# Power.net
KiCad netlist of a schematic drawn in Altium Designer
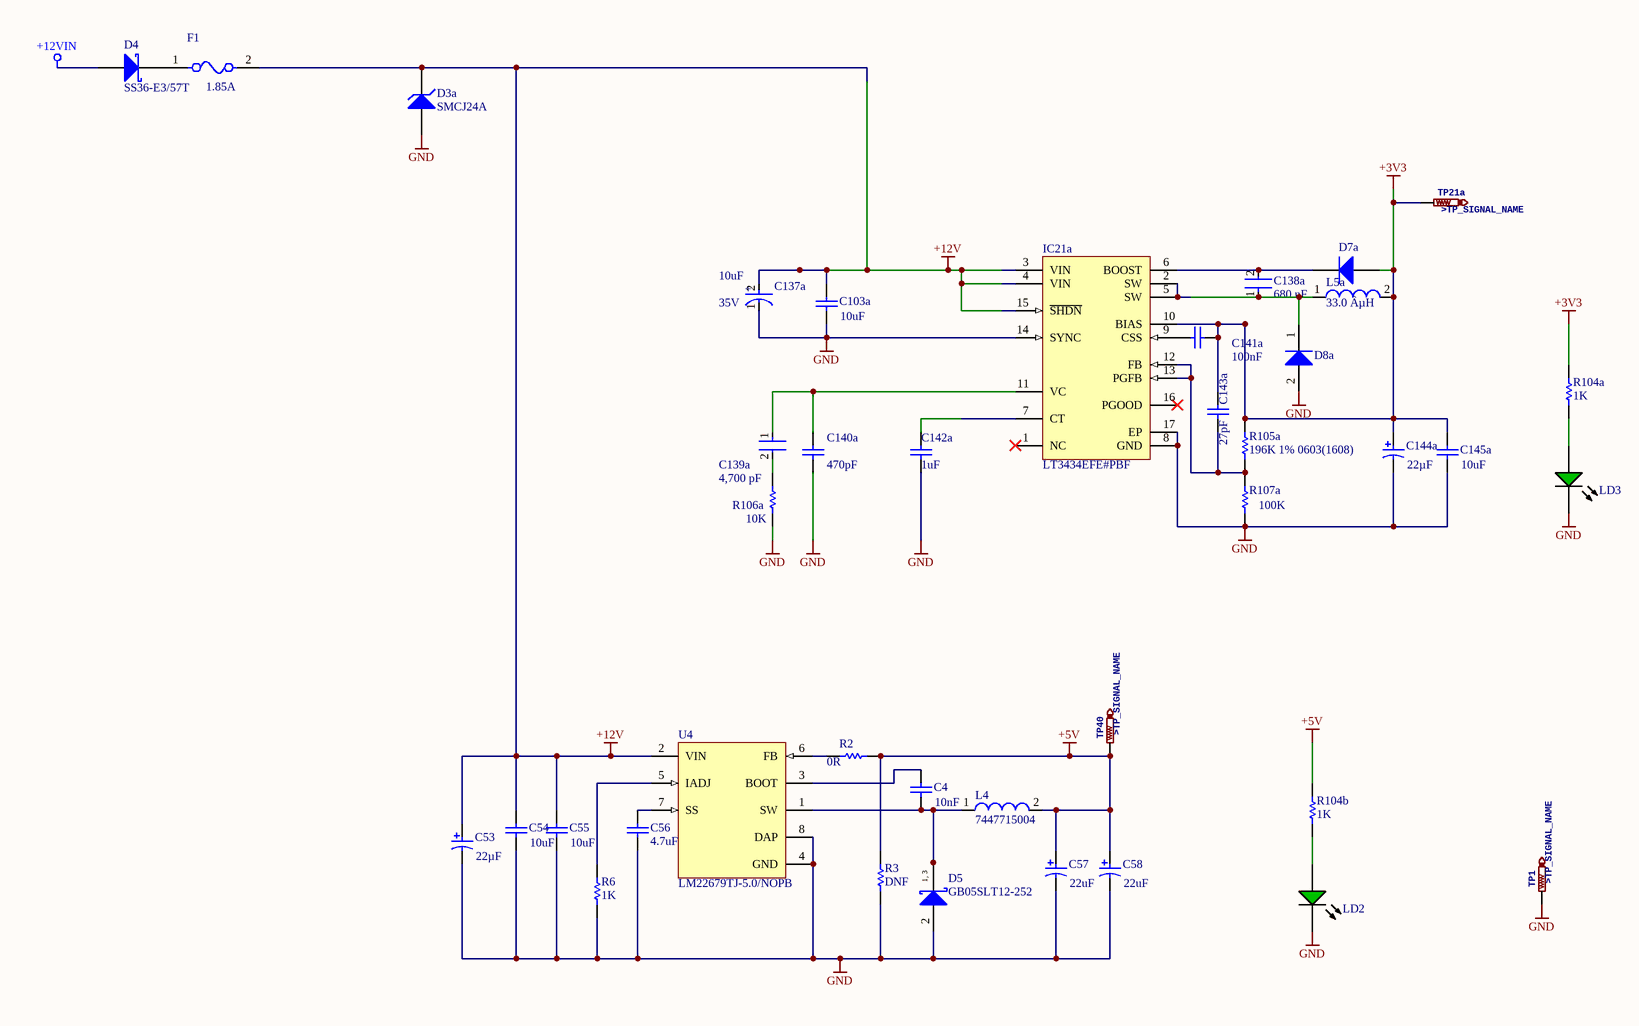
[diagram p0: Power.SchDoc]

(export (version "E")
  (design (tool "Eeschema 10.0.6"))
  (components
    (comp (ref "C4")
      (value "10nF")
      (footprint "CAPC0805(2012)100_N")
      (description "CAP 10nF 100V ±5% 0805 (2012 Metric) Thickness 1mm SMD")
      (fields (field (name "TOLERANCE") "Â±5%") (field (name "Comment") "CAP 10nF 100V 0805(2012)"))
      (libsource (lib "Altium Content Vault") (part "CMP-1036-03852-1"))
    )
    (comp (ref "C53")
      (value "TPSC226K025R0275")
      (footprint "CAPMP6032X28-T_V")
      (description "Low ESR, 22 uF, 25 V, +/- 10%, -55 to 125 degC, 2-Pin SMD, RoHS, Tape and Reel")
      (fields
        (field (name "TOLERANCE") "±10%")
        (field (name "CAPACITANCE") "22µF")
        (field (name "MANUFACTURER") "AVX")
      )
      (libsource (lib "Altium Content Vault") (part "CMP-2000-07295-1"))
    )
    (comp (ref "C54")
      (value "CGA6P3X7S1H106K250AB")
      (footprint "CAPC3225X280X20LL40")
      (description "Chip Capacitor, 10 uF, +/- 10%, 50 V, -55 to 125 degC, 1210 (3225 Metric), RoHS, Tape and Reel")
      (fields
        (field (name "VOLTAGE") "50V")
        (field (name "CAPACITANCE") "10uF")
        (field (name "MANUFACTURER") "TDK")
      )
      (libsource (lib "Altium Content Vault") (part "CMP-2000-07444-1"))
    )
    (comp (ref "C55")
      (value "CGA6P3X7S1H106K250AB")
      (footprint "CAPC3225X280X20LL40")
      (description "Chip Capacitor, 10 uF, +/- 10%, 50 V, -55 to 125 degC, 1210 (3225 Metric), RoHS, Tape and Reel")
      (fields
        (field (name "VOLTAGE") "50V")
        (field (name "CAPACITANCE") "10uF")
        (field (name "MANUFACTURER") "TDK")
      )
      (libsource (lib "Altium Content Vault") (part "CMP-2000-07444-1"))
    )
    (comp (ref "C56")
      (value "4.7uF")
      (footprint "CAPC1206(3216)190_M")
      (description "CAP 4.7uF 25V ±20% 1206 (3216 Metric) Thickness 1.9mm SMD")
      (fields (field (name "TOLERANCE") "Â±20%") (field (name "Comment") "CAP 4.7uF 25V 1206(3216)"))
      (libsource (lib "Altium Content Vault") (part "CMP-1037-04919-1"))
    )
    (comp (ref "C57")
      (value "TPSE227M016R0100")
      (footprint "CAPMP7344X43-T_V")
      (description "Low ESR, 220 uF, 16 V, +/- 20%, -55 to 125 degC, 2-Pin SMD, RoHS, Tape and Reel")
      (fields
        (field (name "VOLTAGE") "16VDC")
        (field (name "CAPACITANCE") "22uF")
        (field (name "MANUFACTURER") "AVX")
      )
      (libsource (lib "Altium Content Vault") (part "CMP-2000-07312-1"))
    )
    (comp (ref "C58")
      (value "TPSE227M016R0100")
      (footprint "CAPMP7344X43-T_V")
      (description "Low ESR, 220 uF, 16 V, +/- 20%, -55 to 125 degC, 2-Pin SMD, RoHS, Tape and Reel")
      (fields
        (field (name "VOLTAGE") "16VDC")
        (field (name "CAPACITANCE") "22uF")
        (field (name "MANUFACTURER") "AVX")
      )
      (libsource (lib "Altium Content Vault") (part "CMP-2000-07312-1"))
    )
    (comp (ref "C103a")
      (value "CGA6P3X7S1H106K250AB")
      (footprint "CAPC3225X280X20LL40")
      (description "Chip Capacitor, 10 uF, +/- 10%, 50 V, -55 to 125 degC, 1210 (3225 Metric), RoHS, Tape and Reel")
      (fields
        (field (name "VOLTAGE") "50V")
        (field (name "CAPACITANCE") "10uF")
        (field (name "MANUFACTURER") "TDK")
      )
      (libsource (lib "Altium Content Vault") (part "CMP-2000-07444-1"))
    )
    (comp (ref "C137a")
      (value "10uF")
      (footprint "FP-TAJD-MFG")
      (description "CAP TANT 10UF 20% 35V 2917")
      (fields
        (field (name "OCTOPART") "https://octopart.com/tajd106m035rnj-avx-3819655")
        (field (name "VOLTAGE RATING") "35V")
        (field (name "MANUFACTURER") "AVX")
      )
      (libsource (lib "Altium Content Vault") (part "CMP-04424-000020-1"))
    )
    (comp (ref "C138a")
      (value "680 nF")
      (footprint "FP-CC0603-DA-MFG")
      (description "CAP CER 0.68UF 16V X7R 0603")
      (fields (field (name "TOLERANCE") "0.1") (field (name "MANUFACTURER") "YAGEO"))
      (libsource (lib "Altium Content Vault") (part "CMP-03422-000082-1"))
    )
    (comp (ref "C139a")
      (value "4,700 pF")
      (footprint "FP-C0603C-CF-MFG")
      (description "CAP CER 4700PF 50V NP0 0603")
      (fields
        (field (name "TOLERANCE") "0.02")
        (field (name "OCTOPART") "https://octopart.com/c0603c472g5gactu-kemet-19050074")
      )
      (libsource (lib "Altium Content Vault") (part "CMP-03020-006967-1"))
    )
    (comp (ref "C140a")
      (value "470pF")
      (footprint "CAPC0603(1608)100_M")
      (description "CAP 470pF 50V ±5% 0603 (1608 Metric) Thickness 1mm SMD")
      (fields (field (name "TOLERANCE") "Â±5%") (field (name "Comment") "CAP 470pF 50V 0603(1608)"))
      (libsource (lib "Altium Content Vault") (part "CMP-1035-01675-1"))
    )
    (comp (ref "C141a")
      (value "100nF")
      (footprint "CAPC0805(2012)100_L")
      (description "CAP 100nF 16V ±5% 0805 (2012 Metric) Thickness 1mm SMD")
      (fields (field (name "TOLERANCE") "Â±5%") (field (name "Comment") "CAP 100nF 16V 0805(2012)"))
      (libsource (lib "Altium Content Vault") (part "CMP-1036-04400-1"))
    )
    (comp (ref "C142a")
      (value "1uF")
      (footprint "CAPC0805(2012)145_N")
      (description "CAP 1uF 6.3V ±10% 0805 (2012 Metric) Thickness 1.45mm SMD")
      (fields (field (name "TOLERANCE") "Â±10%") (field (name "Comment") "CAP 1uF 6.3V 0805(2012)"))
      (libsource (lib "Altium Content Vault") (part "CMP-1036-04731-1"))
    )
    (comp (ref "C143a")
      (value "27pF")
      (footprint "CAPC0603(1608)100_L")
      (description "CAP 27pF 50V ±10% 0603 (1608 Metric) Thickness 1mm SMD")
      (fields (field (name "TOLERANCE") "Â±10%") (field (name "Comment") "CAP 27pF 50V 0603(1608)"))
      (libsource (lib "Altium Content Vault") (part "CMP-1035-00889-1"))
    )
    (comp (ref "C144a")
      (value "TPSC226K025R0275")
      (footprint "CAPMP6032X28-T_V")
      (description "Low ESR, 22 uF, 25 V, +/- 10%, -55 to 125 degC, 2-Pin SMD, RoHS, Tape and Reel")
      (fields
        (field (name "TOLERANCE") "±10%")
        (field (name "CAPACITANCE") "22µF")
        (field (name "MANUFACTURER") "AVX")
      )
      (libsource (lib "Altium Content Vault") (part "CMP-2000-07295-1"))
    )
    (comp (ref "C145a")
      (value "CGA6P3X7S1H106K250AB")
      (footprint "CAPC3225X280X20LL40")
      (description "Chip Capacitor, 10 uF, +/- 10%, 50 V, -55 to 125 degC, 1210 (3225 Metric), RoHS, Tape and Reel")
      (fields
        (field (name "VOLTAGE") "50V")
        (field (name "CAPACITANCE") "10uF")
        (field (name "MANUFACTURER") "TDK")
      )
      (libsource (lib "Altium Content Vault") (part "CMP-2000-07444-1"))
    )
    (comp (ref "D3a")
      (value "SMCJ24A")
      (footprint "FAIR-DO-214AB-2_V")
      (description "Transient Voltage Suppressor, 1500 W, 24 V, 2-Pin SMD, RoHS, Tape and Reel")
      (fields (field (name "MANUFACTURER") "FairchildSemiconductor"))
      (libsource (lib "Altium Content Vault") (part "DZEN-AK-2"))
    )
    (comp (ref "D4")
      (value "SS36-E3/57T")
      (footprint "VISH-DO-214AB-2_V")
      (fields (field (name "MANUFACTURER") "Vishay"))
      (libsource (lib "Altium Content Vault") (part "CMP-2000-07150-1"))
    )
    (comp (ref "D5")
      (value "GB05SLT12-252")
      (footprint "GESC-TO-252-3_M")
      (description "Silicon Carbide Power Schottky Diode, 5 A, -55 to 175 degC, 3-Pin TO-252, RoHS, Bulk")
      (fields (field (name "MANUFACTURER") "GeneSiC Semiconductor"))
      (libsource (lib "Altium Content Vault") (part "DSKY-KAK-3"))
    )
    (comp (ref "D7a")
      (value "JANTX1N4148-1")
      (footprint "MCSM-DO-35-2")
      (description "Glass Axial Switching Diode, 200 mA, 100 V, 2-Pin DO-35, RoHS, Bulk")
      (fields (field (name "PARTNUMBER") "1N4148-1") (field (name "MANUFACTURER") "Microsemi"))
      (libsource (lib "Altium Content Vault") (part "CMP-2000-06494-1"))
    )
    (comp (ref "D8a")
      (value "MBRS3201T3G")
      (footprint "ONSC-SMC-2-403-03_V")
      (description "200 V, 3 A Schottky Fast Soft-Recovery Power Rectifier, 2-Pin SMC, Pb-Free, Tape and Reel")
      (fields (field (name "MANUFACTURER") "On Semiconductor"))
      (libsource (lib "Altium Content Vault") (part "CMP-1055-00379-1"))
    )
    (comp (ref "F1")
      (value "MF-LSMF185/33X-2")
      (footprint "FP-MF-LSMF-MFG")
      (description "PTC RESET FUSE 33V 1.85A 2920")
      (fields
        (field (name "OCTOPART") "https://octopart.com/mf-lsmf185%2F33x-2-bourns-19504849")
        (field (name "MANUFACTURER") "Bourns")
        (field (name "HOLD CURRENT") "1.85A")
      )
      (libsource (lib "Altium Content Vault") (part "CMP-07400-000015-1"))
    )
    (comp (ref "IC21a")
      (value "LT3434EFE#PBF")
      (footprint "LT-FE-16-EPV-BC_M")
      (fields (field (name "MANUFACTURER") "Linear Technology"))
      (libsource (lib "Altium Content Vault") (part "LT-LT3435_LT3434-FE-16"))
    )
    (comp (ref "L4")
      (value "7447715004")
      (footprint "WE-PD-LS")
      (description "SMD-Shielded Power Inductor WE-PD, L = 4.70 µH")
      (libsource (lib "Altium Content Vault") (part "PAS-IND-INDUCTOR-2"))
    )
    (comp (ref "L5a")
      (value "7447715330")
      (footprint "WE-PD-LS")
      (description "SMD-Shielded Power Inductor WE-PD, L = 33.0 µH")
      (fields (field (name "INDUCTANCE") "33.0 ÂµH"))
      (libsource (lib "Altium Content Vault") (part "CMP-0227-00710-1"))
    )
    (comp (ref "LD2")
      (value "SML-LXT0805GW-TR")
      (footprint "LUMX-SML-LXT0805_V")
      (description "LED, GREEN, 565 nm, 2 V, -25 to 80 degC, 2-Pin SMD, RoHS, Tape and Reel")
      (libsource (lib "Altium Content Vault") (part "CMP-1724-00001-1"))
    )
    (comp (ref "LD3")
      (value "SML-LXT0805GW-TR")
      (footprint "LUMX-SML-LXT0805_V")
      (description "LED, GREEN, 565 nm, 2 V, -25 to 80 degC, 2-Pin SMD, RoHS, Tape and Reel")
      (libsource (lib "Altium Content Vault") (part "CMP-1724-00001-1"))
    )
    (comp (ref "R2")
      (value "0R")
      (footprint "RESC1206(3216)_N")
      (description "1K 0.25W 1% 1206 (3216 Metric)  SMD")
      (fields (field (name "POWER") "0.25 W") (field (name "TOLERANCE") "1 %"))
      (libsource (lib "Altium Content Vault") (part "CMP-1014-00510-1"))
    )
    (comp (ref "R3")
      (value "DNF")
      (footprint "RESC1206(3216)_N")
      (description "1K 0.25W 1% 1206 (3216 Metric)  SMD")
      (fields (field (name "POWER") "0.25 W") (field (name "TOLERANCE") "1 %"))
      (libsource (lib "Altium Content Vault") (part "CMP-1014-00510-1"))
    )
    (comp (ref "R6")
      (value "1K")
      (footprint "RESC1206(3216)_N")
      (description "1K 0.25W 1% 1206 (3216 Metric)  SMD")
      (fields (field (name "POWER") "0.25 W") (field (name "TOLERANCE") "1 %"))
      (libsource (lib "Altium Content Vault") (part "CMP-1014-00510-1"))
    )
    (comp (ref "R104a")
      (value "1K")
      (footprint "RESC0805(2012)_M")
      (description "1K 0.125W 1% 0805 (2012 Metric)  SMD")
      (fields (field (name "TOLERANCE") "1 %") (field (name "POWER") "0.125 W"))
      (libsource (lib "Altium Content Vault") (part "CMP-1013-00510-1"))
    )
    (comp (ref "R104b")
      (value "1K")
      (footprint "RESC0805(2012)_M")
      (description "1K 0.125W 1% 0805 (2012 Metric)  SMD")
      (fields (field (name "TOLERANCE") "1 %") (field (name "POWER") "0.125 W"))
      (libsource (lib "Altium Content Vault") (part "CMP-1013-00510-1"))
    )
    (comp (ref "R105a")
      (value "196K 1% 0603(1608)")
      (footprint "RESC0603(1608)_L")
      (description "196K 0.1W 1% 0603 (1608 Metric)  SMD")
      (fields (field (name "POWER") "0.1 W") (field (name "TOLERANCE") "1 %"))
      (libsource (lib "Altium Content Vault") (part "RES"))
    )
    (comp (ref "R106a")
      (value "10K")
      (footprint "RESC0805(2012)_L")
      (description "10K 0.125W 5% 0805 (2012 Metric)  SMD")
      (fields (field (name "TOLERANCE") "5 %") (field (name "POWER") "0.125 W"))
      (libsource (lib "Altium Content Vault") (part "CMP-1013-00098-1"))
    )
    (comp (ref "R107a")
      (value "RC0603FR-07100KL")
      (footprint "RESC1608X55X25ML10T15")
      (description "Chip Resistor, 100 KOhm, +/- 1%, 0.1 W, -55 to 155 degC, 0603 (1608 Metric), RoHS, Tape and Reel")
      (fields
        (field (name "RESISTANCE") "100K")
        (field (name "MANUFACTURER") "Yageo")
        (field (name "TOLERANCE") "1%")
      )
      (libsource (lib "Altium Content Vault") (part "CMP-2100-03662-1"))
    )
    (comp (ref "TP1")
      (value "PTR1PAD1-13")
      (footprint "P1-13")
      (description "TEST PIN")
      (fields (field (name "TP_SIGNAL_NAME") ">TP_SIGNAL_NAME"))
      (libsource (lib "") (part "PTR1PAD1-13_1"))
    )
    (comp (ref "TP21a")
      (value "PTR1PAD1-13")
      (footprint "P1-13")
      (description "TEST PIN")
      (fields (field (name "TP_SIGNAL_NAME") ">TP_SIGNAL_NAME"))
      (libsource (lib "testpad") (part "PTR1PAD1-13"))
    )
    (comp (ref "TP40")
      (value "PTR1PAD1-13")
      (footprint "P1-13")
      (description "TEST PIN")
      (fields (field (name "TP_SIGNAL_NAME") ">TP_SIGNAL_NAME"))
      (libsource (lib "") (part "PTR1PAD1-13_1"))
    )
    (comp (ref "U4")
      (value "LM22679TJ-5.0/NOPB")
      (footprint "NDR0007A_L")
      (fields (field (name "MANUFACTURER") "Texas Instruments"))
      (libsource (lib "Altium Content Vault") (part "PM-REG-LM22679TJ"))
    )
  )
  (nets
    (net (code "1") (name "+3V3") (class "Default")
      (node (ref "C141a") (pin "2") (pinfunction "2_2") (pintype "passive"))
      (node (ref "C143a") (pin "2") (pinfunction "2_2") (pintype "passive"))
      (node (ref "C144a") (pin "1") (pinfunction "1_1") (pintype "passive"))
      (node (ref "C145a") (pin "2") (pinfunction "2_2") (pintype "passive"))
      (node (ref "D7a") (pin "1") (pinfunction "A_1") (pintype "passive"))
      (node (ref "IC21a") (pin "10") (pinfunction "BIAS_10") (pintype "power_in"))
      (node (ref "L5a") (pin "2") (pinfunction "2_2") (pintype "passive"))
      (node (ref "R104a") (pin "2") (pinfunction "2_2") (pintype "passive"))
      (node (ref "R105a") (pin "1") (pinfunction "1_1") (pintype "passive"))
      (node (ref "TP21a") (pin "TP") (pinfunction "TP_TP") (pintype "passive"))
    )
    (net (code "2") (name "+5V") (class "Default")
      (node (ref "C57") (pin "1") (pinfunction "1_1") (pintype "passive"))
      (node (ref "C58") (pin "1") (pinfunction "1_1") (pintype "passive"))
      (node (ref "L4") (pin "2") (pinfunction "2_2") (pintype "passive"))
      (node (ref "R104b") (pin "2") (pinfunction "2_2") (pintype "passive"))
      (node (ref "R2") (pin "2") (pinfunction "2_2") (pintype "passive"))
      (node (ref "R3") (pin "2") (pinfunction "2_2") (pintype "passive"))
      (node (ref "TP40") (pin "TP") (pinfunction "TP_TP") (pintype "passive"))
    )
    (net (code "3") (name "+12V") (class "Default")
      (node (ref "C103a") (pin "2") (pinfunction "2_2") (pintype "passive"))
      (node (ref "C137a") (pin "2") (pinfunction "A_2") (pintype "passive"))
      (node (ref "C53") (pin "1") (pinfunction "1_1") (pintype "passive"))
      (node (ref "C54") (pin "2") (pinfunction "2_2") (pintype "passive"))
      (node (ref "C55") (pin "2") (pinfunction "2_2") (pintype "passive"))
      (node (ref "D3a") (pin "2") (pinfunction "K_2") (pintype "passive"))
      (node (ref "F1") (pin "2") (pinfunction "2_2") (pintype "passive"))
      (node (ref "IC21a") (pin "15") (pinfunction "~{SHDN}_15") (pintype "input"))
      (node (ref "IC21a") (pin "3") (pinfunction "VIN_3") (pintype "power_in"))
      (node (ref "IC21a") (pin "4") (pinfunction "VIN_4") (pintype "power_in"))
      (node (ref "U4") (pin "2") (pinfunction "VIN_2") (pintype "power_in"))
    )
    (net (code "4") (name "+12VIN") (class "Default")
      (node (ref "D4") (pin "1") (pinfunction "A_1") (pintype "passive"))
    )
    (net (code "5") (name "GND") (class "Default")
      (node (ref "C103a") (pin "1") (pinfunction "1_1") (pintype "passive"))
      (node (ref "C137a") (pin "1") (pinfunction "C_1") (pintype "passive"))
      (node (ref "C140a") (pin "1") (pinfunction "1_1") (pintype "passive"))
      (node (ref "C142a") (pin "1") (pinfunction "1_1") (pintype "passive"))
      (node (ref "C144a") (pin "2") (pinfunction "2_2") (pintype "passive"))
      (node (ref "C145a") (pin "1") (pinfunction "1_1") (pintype "passive"))
      (node (ref "C53") (pin "2") (pinfunction "2_2") (pintype "passive"))
      (node (ref "C54") (pin "1") (pinfunction "1_1") (pintype "passive"))
      (node (ref "C55") (pin "1") (pinfunction "1_1") (pintype "passive"))
      (node (ref "C56") (pin "1") (pinfunction "1_1") (pintype "passive"))
      (node (ref "C57") (pin "2") (pinfunction "2_2") (pintype "passive"))
      (node (ref "C58") (pin "2") (pinfunction "2_2") (pintype "passive"))
      (node (ref "D3a") (pin "1") (pinfunction "A_1") (pintype "passive"))
      (node (ref "D5") (pin "2") (pinfunction "A_2") (pintype "passive"))
      (node (ref "D8a") (pin "2") (pinfunction "A_2") (pintype "passive"))
      (node (ref "IC21a") (pin "14") (pinfunction "SYNC_14") (pintype "input"))
      (node (ref "IC21a") (pin "17") (pinfunction "EP_17") (pintype "power_in"))
      (node (ref "IC21a") (pin "8") (pinfunction "GND_8") (pintype "power_in"))
      (node (ref "LD2") (pin "2") (pinfunction "K_2") (pintype "passive"))
      (node (ref "LD3") (pin "2") (pinfunction "K_2") (pintype "passive"))
      (node (ref "R106a") (pin "1") (pinfunction "1_1") (pintype "passive"))
      (node (ref "R107a") (pin "1") (pinfunction "1_1") (pintype "passive"))
      (node (ref "R3") (pin "1") (pinfunction "1_1") (pintype "passive"))
      (node (ref "R6") (pin "1") (pinfunction "1_1") (pintype "passive"))
      (node (ref "TP1") (pin "TP") (pinfunction "TP_TP") (pintype "passive"))
      (node (ref "U4") (pin "4") (pinfunction "GND_4") (pintype "power_in"))
      (node (ref "U4") (pin "8") (pinfunction "DAP_8") (pintype "power_in"))
    )
    (net (code "6") (name "Net-(C139a-Pad2)") (class "Default")
      (node (ref "C139a") (pin "2") (pinfunction "2_2") (pintype "passive"))
      (node (ref "R106a") (pin "2") (pinfunction "2_2") (pintype "passive"))
    )
    (net (code "7") (name "Net-(D4-K)") (class "Default")
      (node (ref "D4") (pin "2") (pinfunction "K_2") (pintype "passive"))
      (node (ref "F1") (pin "1") (pinfunction "1_1") (pintype "passive"))
    )
    (net (code "8") (name "Net-(D7a-K)") (class "Default")
      (node (ref "C138a") (pin "2") (pinfunction "2_2") (pintype "passive"))
      (node (ref "D7a") (pin "2") (pinfunction "K_2") (pintype "passive"))
      (node (ref "IC21a") (pin "6") (pinfunction "BOOST_6") (pintype "passive"))
    )
    (net (code "9") (name "Net-(D8a-K)") (class "Default")
      (node (ref "C138a") (pin "1") (pinfunction "1_1") (pintype "passive"))
      (node (ref "D8a") (pin "1") (pinfunction "K_1") (pintype "passive"))
      (node (ref "IC21a") (pin "2") (pinfunction "SW_2") (pintype "power_in"))
      (node (ref "IC21a") (pin "5") (pinfunction "SW_5") (pintype "power_in"))
      (node (ref "L5a") (pin "1") (pinfunction "1_1") (pintype "passive"))
    )
    (net (code "10") (name "Net-(IC21a-CSS)") (class "Default")
      (node (ref "C141a") (pin "1") (pinfunction "1_1") (pintype "passive"))
      (node (ref "IC21a") (pin "9") (pinfunction "CSS_9") (pintype "input"))
    )
    (net (code "11") (name "Net-(IC21a-CT)") (class "Default")
      (node (ref "C142a") (pin "2") (pinfunction "2_2") (pintype "passive"))
      (node (ref "IC21a") (pin "7") (pinfunction "CT_7") (pintype "passive"))
    )
    (net (code "12") (name "Net-(IC21a-FB)") (class "Default")
      (node (ref "C143a") (pin "1") (pinfunction "1_1") (pintype "passive"))
      (node (ref "IC21a") (pin "12") (pinfunction "FB_12") (pintype "input"))
      (node (ref "IC21a") (pin "13") (pinfunction "PGFB_13") (pintype "input"))
      (node (ref "R105a") (pin "2") (pinfunction "2_2") (pintype "passive"))
      (node (ref "R107a") (pin "2") (pinfunction "2_2") (pintype "passive"))
    )
    (net (code "13") (name "Net-(IC21a-VC)") (class "Default")
      (node (ref "C139a") (pin "1") (pinfunction "1_1") (pintype "passive"))
      (node (ref "C140a") (pin "2") (pinfunction "2_2") (pintype "passive"))
      (node (ref "IC21a") (pin "11") (pinfunction "VC_11") (pintype "passive"))
    )
    (net (code "14") (name "Net-(LD2-A)") (class "Default")
      (node (ref "LD2") (pin "1") (pinfunction "A_1") (pintype "passive"))
      (node (ref "R104b") (pin "1") (pinfunction "1_1") (pintype "passive"))
    )
    (net (code "15") (name "Net-(LD3-A)") (class "Default")
      (node (ref "LD3") (pin "1") (pinfunction "A_1") (pintype "passive"))
      (node (ref "R104a") (pin "1") (pinfunction "1_1") (pintype "passive"))
    )
    (net (code "16") (name "Net-(U4-BOOT)") (class "Default")
      (node (ref "C4") (pin "2") (pinfunction "2_2") (pintype "passive"))
      (node (ref "U4") (pin "3") (pinfunction "BOOT_3") (pintype "passive"))
    )
    (net (code "17") (name "Net-(U4-FB)") (class "Default")
      (node (ref "R2") (pin "1") (pinfunction "1_1") (pintype "passive"))
      (node (ref "U4") (pin "6") (pinfunction "FB_6") (pintype "input"))
    )
    (net (code "18") (name "Net-(U4-IADJ)") (class "Default")
      (node (ref "R6") (pin "2") (pinfunction "2_2") (pintype "passive"))
      (node (ref "U4") (pin "5") (pinfunction "IADJ_5") (pintype "input"))
    )
    (net (code "19") (name "Net-(U4-SS)") (class "Default")
      (node (ref "C56") (pin "2") (pinfunction "2_2") (pintype "passive"))
      (node (ref "U4") (pin "7") (pinfunction "SS_7") (pintype "input"))
    )
    (net (code "20") (name "Net-(U4-SW)") (class "Default")
      (node (ref "C4") (pin "1") (pinfunction "1_1") (pintype "passive"))
      (node (ref "D5") (pin "1") (pinfunction "K_1") (pintype "passive"))
      (node (ref "D5") (pin "3") (pinfunction "K_3") (pintype "passive"))
      (node (ref "L4") (pin "1") (pinfunction "1_1") (pintype "passive"))
      (node (ref "U4") (pin "1") (pinfunction "SW_1") (pintype "power_in"))
    )
    (net (code "21") (name "unconnected-(IC21a-NC-Pad1)") (class "Default")
      (node (ref "IC21a") (pin "1") (pinfunction "NC_1") (pintype "passive+no_connect"))
    )
    (net (code "22") (name "unconnected-(IC21a-PGOOD-Pad16)") (class "Default")
      (node (ref "IC21a") (pin "16") (pinfunction "PGOOD_16") (pintype "tri_state+no_connect"))
    )
  )
)
